# Peripherals.net
KiCad netlist of a schematic drawn in Altium Designer
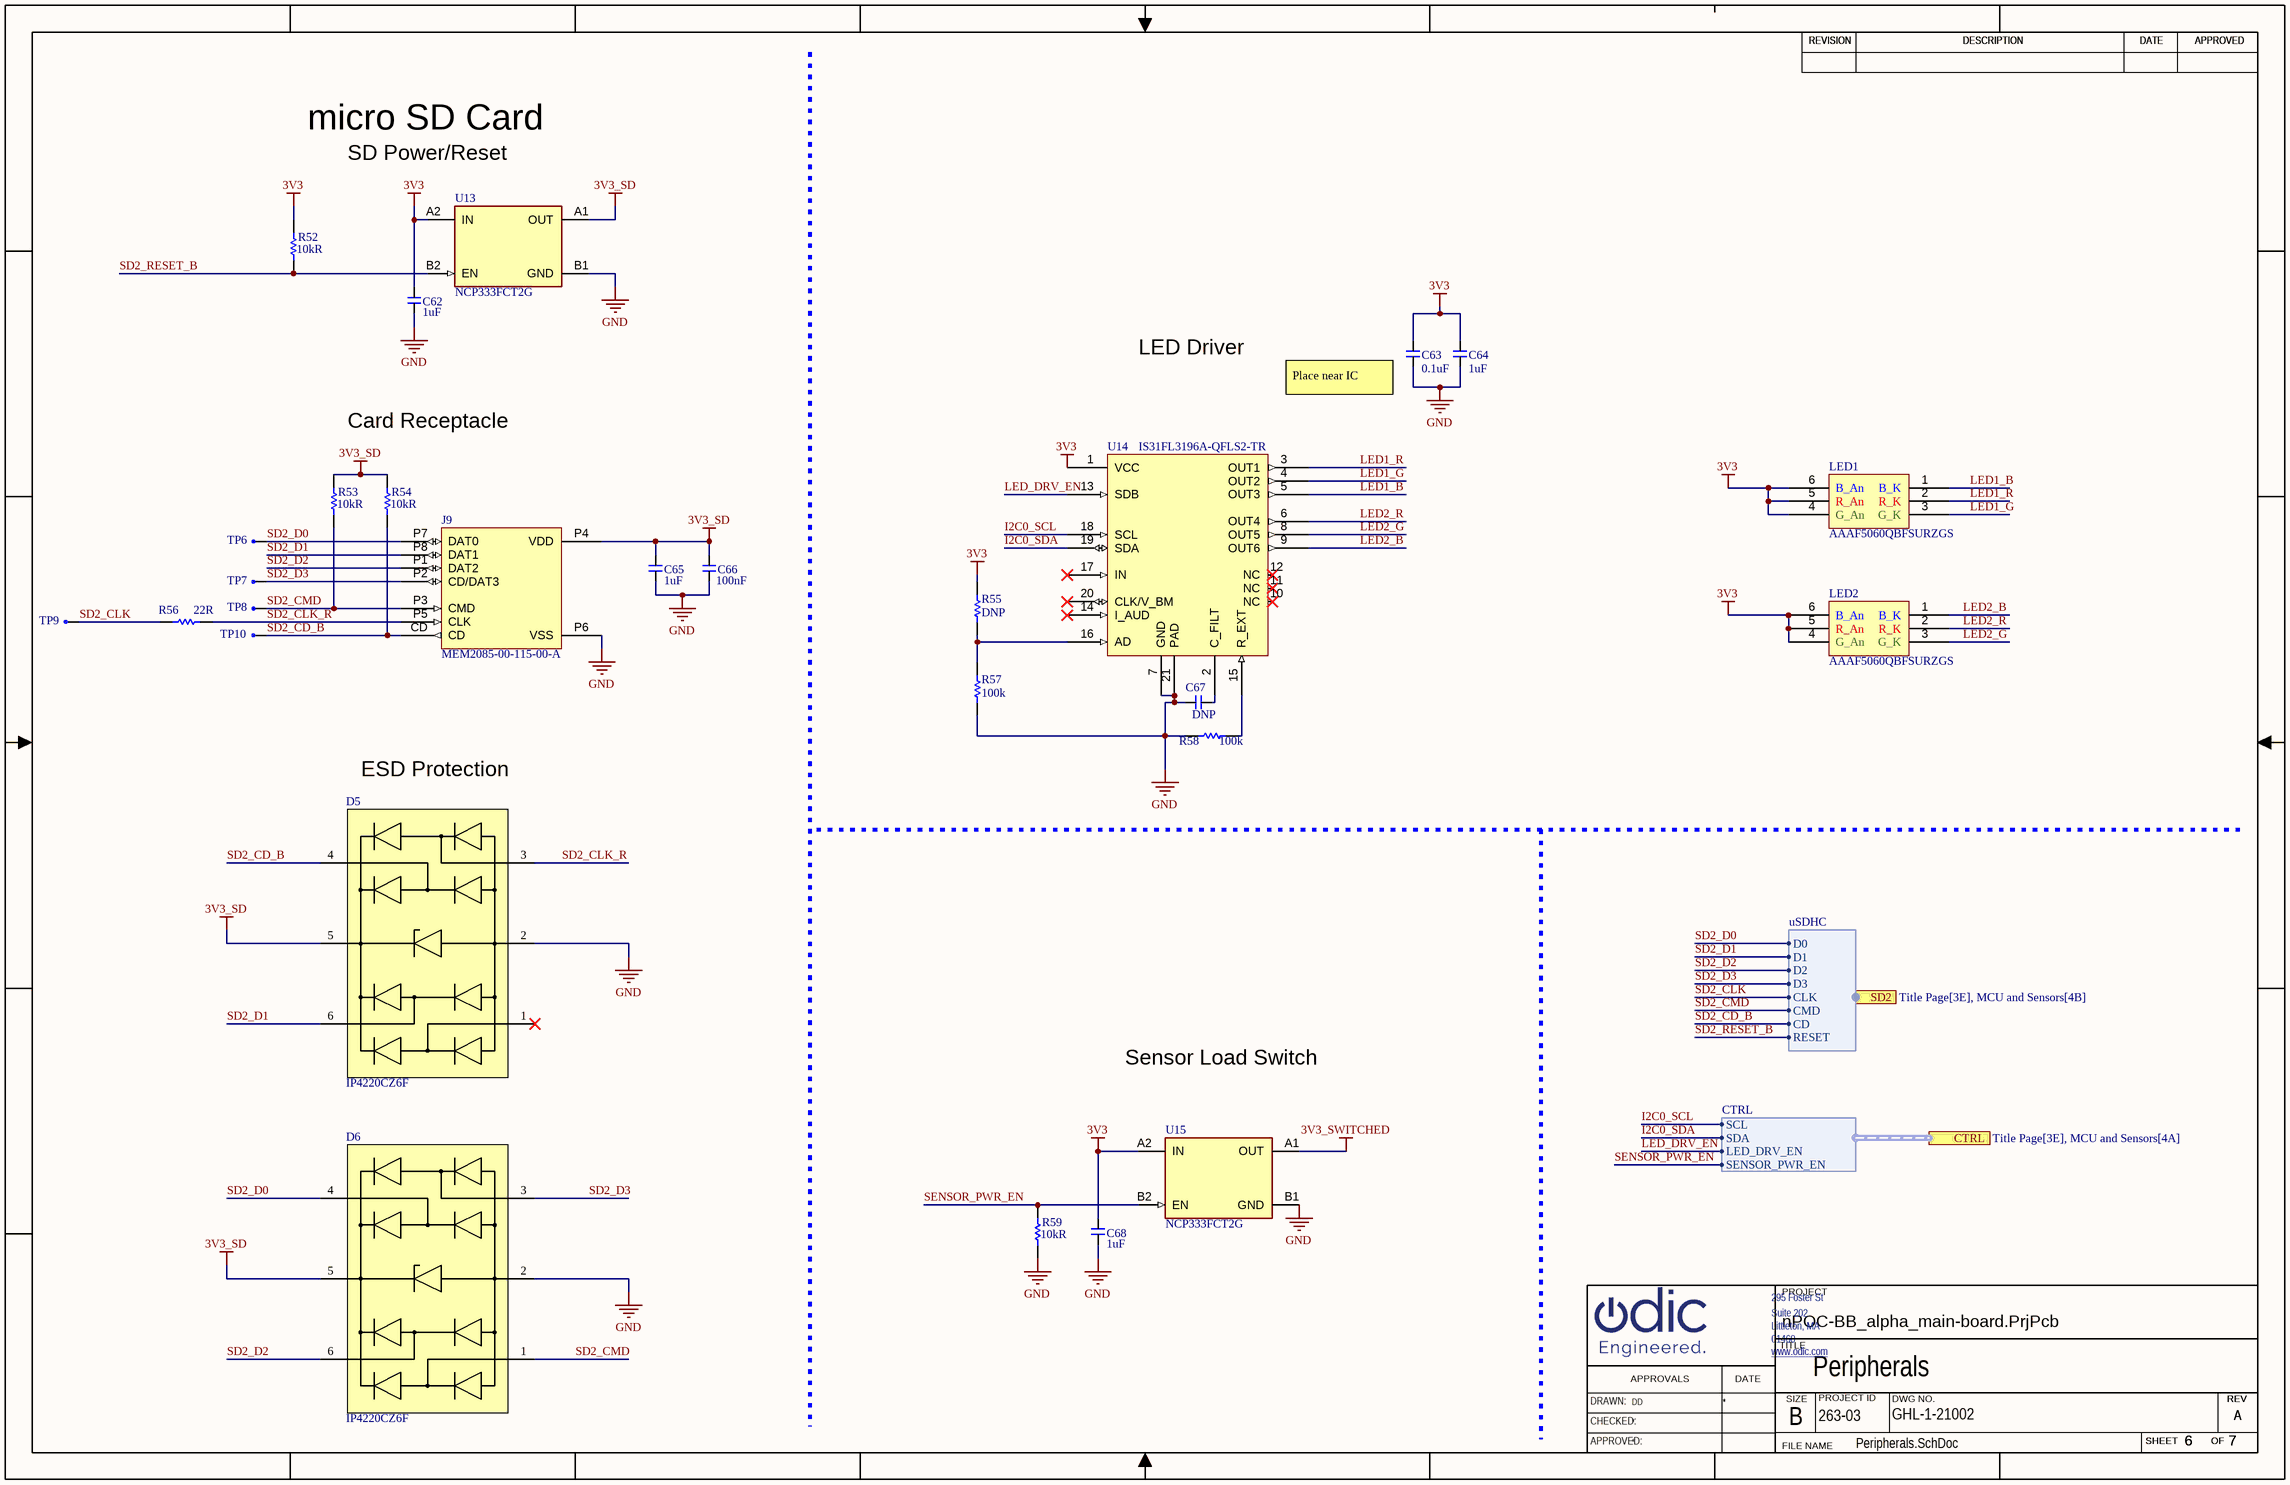
[diagram p0: Peripherals.SchDoc]

(export (version "E")
  (design (tool "Eeschema 10.0.6"))
  (components
    (comp (ref "C62")
      (value "C0402_1u_6V3_10pct")
      (footprint "C0402")
      (description "Cap Ceramic 1uF 6.3V X5R 10% SMD 0402 85C Paper T/R")
      (fields (field (name "CAPACITANCE") "1uF") (field (name "TOLERANCE") "10%"))
      (libsource (lib "Odic Inc") (part "cAP"))
    )
    (comp (ref "C63")
      (value "0.1uF")
      (footprint "C0402")
      (description "Cap Ceramic 0.1uF 25V X5R 10% Pad SMD 0402 Multi Layer Ceramic Capacitor (MLCC)")
      (fields (field (name "VOLTAGE") "25V") (field (name "TOLERANCE") "10%"))
      (libsource (lib "Odic Inc") (part "cAP"))
    )
    (comp (ref "C64")
      (value "1uF")
      (footprint "C0402")
      (description "CAP CER 1UF 16V X5R 0402")
      (fields (field (name "VOLTAGE") "16V") (field (name "TOLERANCE") "10%"))
      (libsource (lib "Odic Inc") (part "cAP"))
    )
    (comp (ref "C65")
      (value "C0402_1u_6V3_10pct")
      (footprint "C0402")
      (description "Cap Ceramic 1uF 6.3V X5R 10% SMD 0402 85C Paper T/R")
      (fields (field (name "CAPACITANCE") "1uF") (field (name "TOLERANCE") "10%"))
      (libsource (lib "Odic Inc") (part "cAP"))
    )
    (comp (ref "C66")
      (value "100nF")
      (footprint "C0402")
      (description "Ceramic capacitor SMD 0402 100nF 16V X7R 10%")
      (fields (field (name "VOLTAGE") "16V") (field (name "TOLERANCE") "10%"))
      (libsource (lib "Odic Inc") (part "cAP"))
    )
    (comp (ref "C67")
      (value "N/A")
      (footprint "C0603")
      (description "DNP CAP")
      (fields
        (field (name "MANUFACTURER") "Samsung")
        (field (name "MANUFACTURER PART NUMBER") "CL10B104KB8NNWC")
        (field (name "INSTALL") "DNP")
      )
      (libsource (lib "Odic Inc") (part "cAP"))
    )
    (comp (ref "C68")
      (value "C0402_1u_6V3_10pct")
      (footprint "C0402")
      (description "Cap Ceramic 1uF 6.3V X5R 10% SMD 0402 85C Paper T/R")
      (fields (field (name "CAPACITANCE") "1uF") (field (name "TOLERANCE") "10%"))
      (libsource (lib "Odic Inc") (part "cAP"))
    )
    (comp (ref "D5")
      (value "IP4220CZ6F")
      (footprint "SOT23-6PIN")
      (description "IC USB DUAL ESD PROTEC 6TSOP")
      (libsource (lib "Odic Inc") (part "IP4220CZ6F-symbol"))
    )
    (comp (ref "D6")
      (value "IP4220CZ6F")
      (footprint "SOT23-6PIN")
      (description "IC USB DUAL ESD PROTEC 6TSOP")
      (libsource (lib "Odic Inc") (part "IP4220CZ6F-symbol"))
    )
    (comp (ref "J9")
      (value "MEM2085-00-115-00-A")
      (footprint "GCT_MEM2085-00-115-00-A_REV0.2")
      (description "9 (8 + 1) Position Secure Digital microSD SMT Right Angle Card Connector")
      (libsource (lib "Odic Inc") (part "MEM2085-00-115-00-A-Symbol-1"))
    )
    (comp (ref "LED1")
      (value "AAAF5060QBFSURZGS")
      (footprint "led6_smt_5x6mm")
      (description "Blue/Red/Green 100º 400/800/1000 mcd Clear Surface Mount LED Lamp")
      (libsource (lib "Odic Inc") (part "AAAF5060QBFSURZGS-Symbol-1"))
    )
    (comp (ref "LED2")
      (value "AAAF5060QBFSURZGS")
      (footprint "led6_smt_5x6mm")
      (description "Blue/Red/Green 100º 400/800/1000 mcd Clear Surface Mount LED Lamp")
      (libsource (lib "Odic Inc") (part "AAAF5060QBFSURZGS-Symbol-1"))
    )
    (comp (ref "R52")
      (value "R0402_10k_1pct")
      (footprint "R0402")
      (description "Res Thick Film 0402 10K Ohm 1% 1/16W ±100ppm/°C Molded SMD SMD T/R")
      (fields (field (name "RESISTANCE") "10kR") (field (name "TOLERANCE") "1%"))
      (libsource (lib "Odic Inc") (part "RES"))
    )
    (comp (ref "R53")
      (value "R0402_10k_1pct")
      (footprint "R0402")
      (description "Res Thick Film 0402 10K Ohm 1% 1/16W ±100ppm/°C Molded SMD SMD T/R")
      (fields (field (name "RESISTANCE") "10kR") (field (name "TOLERANCE") "1%"))
      (libsource (lib "Odic Inc") (part "RES"))
    )
    (comp (ref "R54")
      (value "R0402_10k_1pct")
      (footprint "R0402")
      (description "Res Thick Film 0402 10K Ohm 1% 1/16W ±100ppm/°C Molded SMD SMD T/R")
      (fields (field (name "RESISTANCE") "10kR") (field (name "TOLERANCE") "1%"))
      (libsource (lib "Odic Inc") (part "RES"))
    )
    (comp (ref "R55")
      (value "DNP")
      (footprint "R0402")
      (description "Unpopulated 0402 pads. No part number associated with this \"component\"")
      (libsource (lib "Odic Inc") (part "RES"))
    )
    (comp (ref "R56")
      (value "R0402_22R_1pct")
      (footprint "R0402")
      (description "Res SMD 22 Ohm 1% 1/16W 0402")
      (fields (field (name "RESISTANCE") "22R"))
      (libsource (lib "Odic Inc") (part "RES"))
    )
    (comp (ref "R57")
      (value "100k")
      (footprint "R0402")
      (description "Res General Purpose Thick Film 0402 100K Ohm 1% 1/16W ±100ppm/°C Molded SMD Paper T/R")
      (fields (field (name "TOLERANCE") "1%"))
      (libsource (lib "Odic Inc") (part "RES"))
    )
    (comp (ref "R58")
      (value "100k")
      (footprint "R0402")
      (description "Res General Purpose Thick Film 0402 100K Ohm 1% 1/16W ±100ppm/°C Molded SMD Paper T/R")
      (fields (field (name "TOLERANCE") "1%"))
      (libsource (lib "Odic Inc") (part "RES"))
    )
    (comp (ref "R59")
      (value "R0402_10k_1pct")
      (footprint "R0402")
      (description "Res Thick Film 0402 10K Ohm 1% 1/16W ±100ppm/°C Molded SMD SMD T/R")
      (fields (field (name "RESISTANCE") "10kR") (field (name "TOLERANCE") "1%"))
      (libsource (lib "Odic Inc") (part "RES"))
    )
    (comp (ref "TP6")
      (value "TPC30")
      (footprint "tpc30")
      (description "Test Point Circle 30")
      (libsource (lib "Odic Inc") (part "TPC"))
    )
    (comp (ref "TP7")
      (value "TPC30")
      (footprint "tpc30")
      (description "Test Point Circle 30")
      (libsource (lib "Odic Inc") (part "TPC"))
    )
    (comp (ref "TP8")
      (value "TPC30")
      (footprint "tpc30")
      (description "Test Point Circle 30")
      (libsource (lib "Odic Inc") (part "TPC"))
    )
    (comp (ref "TP9")
      (value "TPC30")
      (footprint "tpc30")
      (description "Test Point Circle 30")
      (libsource (lib "Odic Inc") (part "TPC"))
    )
    (comp (ref "TP10")
      (value "TPC30")
      (footprint "tpc30")
      (description "Test Point Circle 30")
      (libsource (lib "Odic Inc") (part "TPC"))
    )
    (comp (ref "U13")
      (value "NCP333FCT2G")
      (footprint "bga4_p743xp743_p4mm")
      (description "IC LOAD SWITCH W/DIS 1.5A 4WLCSP")
      (libsource (lib "Odic Inc") (part "97019fd276bc7644be76e1f711e9589"))
    )
    (comp (ref "U14")
      (value "IS31FL3196A-QFLS2-TR")
      (footprint "qfn20_3x3_p4mm")
      (description "6-Channel Light Effect LED Driver with I2C Interface 2.7V to 5.5V Input 20-Pin QFN T/R")
      (libsource (lib "Odic Inc") (part "IS31FL3196A-QFLS2-TR-Symbol-1"))
    )
    (comp (ref "U15")
      (value "NCP333FCT2G")
      (footprint "bga4_p743xp743_p4mm")
      (description "IC LOAD SWITCH W/DIS 1.5A 4WLCSP")
      (libsource (lib "Odic Inc") (part "97019fd276bc7644be76e1f711e9589"))
    )
  )
  (nets
    (net (code "3") (name "/I2C0_SCL") (class "Default")
      (node (ref "U14") (pin "18") (pinfunction "SCL_18") (pintype "input"))
    )
    (net (code "4") (name "/I2C0_SDA") (class "Default")
      (node (ref "U14") (pin "19") (pinfunction "SDA_19") (pintype "bidirectional"))
    )
    (net (code "5") (name "/LED1_B") (class "Default")
      (node (ref "LED1") (pin "1") (pinfunction "B_K_1") (pintype "passive"))
      (node (ref "U14") (pin "5") (pinfunction "OUT3_5") (pintype "output"))
    )
    (net (code "6") (name "/LED1_G") (class "Default")
      (node (ref "LED1") (pin "3") (pinfunction "G_K_3") (pintype "passive"))
      (node (ref "U14") (pin "4") (pinfunction "OUT2_4") (pintype "output"))
    )
    (net (code "7") (name "/LED1_R") (class "Default")
      (node (ref "LED1") (pin "2") (pinfunction "R_K_2") (pintype "passive"))
      (node (ref "U14") (pin "3") (pinfunction "OUT1_3") (pintype "output"))
    )
    (net (code "8") (name "/LED2_B") (class "Default")
      (node (ref "LED2") (pin "1") (pinfunction "B_K_1") (pintype "passive"))
      (node (ref "U14") (pin "9") (pinfunction "OUT6_9") (pintype "output"))
    )
    (net (code "9") (name "/LED2_G") (class "Default")
      (node (ref "LED2") (pin "3") (pinfunction "G_K_3") (pintype "passive"))
      (node (ref "U14") (pin "8") (pinfunction "OUT5_8") (pintype "output"))
    )
    (net (code "10") (name "/LED2_R") (class "Default")
      (node (ref "LED2") (pin "2") (pinfunction "R_K_2") (pintype "passive"))
      (node (ref "U14") (pin "6") (pinfunction "OUT4_6") (pintype "output"))
    )
    (net (code "11") (name "/LED_DRV_EN") (class "Default")
      (node (ref "U14") (pin "13") (pinfunction "SDB_13") (pintype "input"))
    )
    (net (code "12") (name "/SD2_CD_B") (class "Default")
      (node (ref "D5") (pin "4") (pinfunction "I/O3_4") (pintype "passive"))
      (node (ref "J9") (pin "CD") (pinfunction "CD_CD") (pintype "output"))
      (node (ref "R54") (pin "2") (pinfunction "2_2") (pintype "passive"))
      (node (ref "TP10") (pin "1") (pinfunction "1_1") (pintype "passive"))
    )
    (net (code "13") (name "/SD2_CLK") (class "Default")
      (node (ref "R56") (pin "1") (pinfunction "1_1") (pintype "passive"))
      (node (ref "TP9") (pin "1") (pinfunction "1_1") (pintype "passive"))
    )
    (net (code "14") (name "/SD2_CLK_R") (class "Default")
      (node (ref "D5") (pin "3") (pinfunction "I/O2_3") (pintype "passive"))
      (node (ref "J9") (pin "P5") (pinfunction "CLK_P5") (pintype "input"))
      (node (ref "R56") (pin "2") (pinfunction "2_2") (pintype "passive"))
    )
    (net (code "15") (name "/SD2_CMD") (class "Default")
      (node (ref "D6") (pin "1") (pinfunction "I/O1_1") (pintype "passive"))
      (node (ref "J9") (pin "P3") (pinfunction "CMD_P3") (pintype "input"))
      (node (ref "R53") (pin "2") (pinfunction "2_2") (pintype "passive"))
      (node (ref "TP8") (pin "1") (pinfunction "1_1") (pintype "passive"))
    )
    (net (code "16") (name "/SD2_D0") (class "Default")
      (node (ref "D6") (pin "4") (pinfunction "I/O3_4") (pintype "passive"))
      (node (ref "J9") (pin "P7") (pinfunction "DAT0_P7") (pintype "bidirectional"))
      (node (ref "TP6") (pin "1") (pinfunction "1_1") (pintype "passive"))
    )
    (net (code "17") (name "/SD2_D1") (class "Default")
      (node (ref "D5") (pin "6") (pinfunction "I/O4_6") (pintype "passive"))
      (node (ref "J9") (pin "P8") (pinfunction "DAT1_P8") (pintype "bidirectional"))
    )
    (net (code "18") (name "/SD2_D2") (class "Default")
      (node (ref "D6") (pin "6") (pinfunction "I/O4_6") (pintype "passive"))
      (node (ref "J9") (pin "P1") (pinfunction "DAT2_P1") (pintype "bidirectional"))
    )
    (net (code "19") (name "/SD2_D3") (class "Default")
      (node (ref "D6") (pin "3") (pinfunction "I/O2_3") (pintype "passive"))
      (node (ref "J9") (pin "P2") (pinfunction "CD/DAT3_P2") (pintype "bidirectional"))
      (node (ref "TP7") (pin "1") (pinfunction "1_1") (pintype "passive"))
    )
    (net (code "20") (name "/SD2_RESET_B") (class "Default")
      (node (ref "R52") (pin "2") (pinfunction "2_2") (pintype "passive"))
      (node (ref "U13") (pin "B2") (pinfunction "EN_B2") (pintype "input"))
    )
    (net (code "21") (name "/SENSOR_PWR_EN") (class "Default")
      (node (ref "R59") (pin "1") (pinfunction "1_1") (pintype "passive"))
      (node (ref "U15") (pin "B2") (pinfunction "EN_B2") (pintype "input"))
    )
    (net (code "24") (name "3V3") (class "Default")
      (node (ref "C62") (pin "2") (pinfunction "2_2") (pintype "passive"))
      (node (ref "C63") (pin "2") (pinfunction "2_2") (pintype "passive"))
      (node (ref "C64") (pin "2") (pinfunction "2_2") (pintype "passive"))
      (node (ref "C68") (pin "2") (pinfunction "2_2") (pintype "passive"))
      (node (ref "LED1") (pin "4") (pinfunction "G_An_4") (pintype "passive"))
      (node (ref "LED1") (pin "5") (pinfunction "R_An_5") (pintype "passive"))
      (node (ref "LED1") (pin "6") (pinfunction "B_An_6") (pintype "passive"))
      (node (ref "LED2") (pin "4") (pinfunction "G_An_4") (pintype "passive"))
      (node (ref "LED2") (pin "5") (pinfunction "R_An_5") (pintype "passive"))
      (node (ref "LED2") (pin "6") (pinfunction "B_An_6") (pintype "passive"))
      (node (ref "R52") (pin "1") (pinfunction "1_1") (pintype "passive"))
      (node (ref "R55") (pin "2") (pinfunction "2_2") (pintype "passive"))
      (node (ref "U13") (pin "A2") (pinfunction "IN_A2") (pintype "power_in"))
      (node (ref "U14") (pin "1") (pinfunction "VCC_1") (pintype "power_in"))
      (node (ref "U15") (pin "A2") (pinfunction "IN_A2") (pintype "power_in"))
    )
    (net (code "25") (name "3V3_SD") (class "Default")
      (node (ref "C65") (pin "2") (pinfunction "2_2") (pintype "passive"))
      (node (ref "C66") (pin "2") (pinfunction "2_2") (pintype "passive"))
      (node (ref "D5") (pin "5") (pinfunction "VP_5") (pintype "power_in"))
      (node (ref "D6") (pin "5") (pinfunction "VP_5") (pintype "power_in"))
      (node (ref "J9") (pin "P4") (pinfunction "VDD_P4") (pintype "passive"))
      (node (ref "R53") (pin "1") (pinfunction "1_1") (pintype "passive"))
      (node (ref "R54") (pin "1") (pinfunction "1_1") (pintype "passive"))
      (node (ref "U13") (pin "A1") (pinfunction "OUT_A1") (pintype "power_in"))
    )
    (net (code "26") (name "3V3_SWITCHED") (class "Default")
      (node (ref "U15") (pin "A1") (pinfunction "OUT_A1") (pintype "power_in"))
    )
    (net (code "27") (name "GND") (class "Default")
      (node (ref "C62") (pin "1") (pinfunction "1_1") (pintype "passive"))
      (node (ref "C63") (pin "1") (pinfunction "1_1") (pintype "passive"))
      (node (ref "C64") (pin "1") (pinfunction "1_1") (pintype "passive"))
      (node (ref "C65") (pin "1") (pinfunction "1_1") (pintype "passive"))
      (node (ref "C66") (pin "1") (pinfunction "1_1") (pintype "passive"))
      (node (ref "C67") (pin "2") (pinfunction "2_2") (pintype "passive"))
      (node (ref "C68") (pin "1") (pinfunction "1_1") (pintype "passive"))
      (node (ref "D5") (pin "2") (pinfunction "GND_2") (pintype "power_in"))
      (node (ref "D6") (pin "2") (pinfunction "GND_2") (pintype "power_in"))
      (node (ref "J9") (pin "P6") (pinfunction "VSS_P6") (pintype "passive"))
      (node (ref "R57") (pin "1") (pinfunction "1_1") (pintype "passive"))
      (node (ref "R58") (pin "2") (pinfunction "2_2") (pintype "passive"))
      (node (ref "R59") (pin "2") (pinfunction "2_2") (pintype "passive"))
      (node (ref "U13") (pin "B1") (pinfunction "GND_B1") (pintype "power_in"))
      (node (ref "U14") (pin "21") (pinfunction "PAD_21") (pintype "passive"))
      (node (ref "U14") (pin "7") (pinfunction "GND_7") (pintype "passive"))
      (node (ref "U15") (pin "B1") (pinfunction "GND_B1") (pintype "power_in"))
    )
    (net (code "28") (name "Net-(U14-AD)") (class "Default")
      (node (ref "R55") (pin "1") (pinfunction "1_1") (pintype "passive"))
      (node (ref "R57") (pin "2") (pinfunction "2_2") (pintype "passive"))
      (node (ref "U14") (pin "16") (pinfunction "AD_16") (pintype "input"))
    )
    (net (code "29") (name "Net-(U14-C_FILT)") (class "Default")
      (node (ref "C67") (pin "1") (pinfunction "1_1") (pintype "passive"))
      (node (ref "U14") (pin "2") (pinfunction "C_FILT_2") (pintype "passive"))
    )
    (net (code "30") (name "Net-(U14-R_EXT)") (class "Default")
      (node (ref "R58") (pin "1") (pinfunction "1_1") (pintype "passive"))
      (node (ref "U14") (pin "15") (pinfunction "R_EXT_15") (pintype "input"))
    )
    (net (code "31") (name "unconnected-(D5-I{slash}O1-Pad1)") (class "Default")
      (node (ref "D5") (pin "1") (pinfunction "I/O1_1") (pintype "passive+no_connect"))
    )
    (net (code "32") (name "unconnected-(U14-CLK{slash}V_BM-Pad20)") (class "Default")
      (node (ref "U14") (pin "20") (pinfunction "CLK/V_BM_20") (pintype "bidirectional+no_connect"))
    )
    (net (code "33") (name "unconnected-(U14-IN-Pad17)") (class "Default")
      (node (ref "U14") (pin "17") (pinfunction "IN_17") (pintype "input+no_connect"))
    )
    (net (code "34") (name "unconnected-(U14-I_AUD-Pad14)") (class "Default")
      (node (ref "U14") (pin "14") (pinfunction "I_AUD_14") (pintype "input+no_connect"))
    )
    (net (code "35") (name "unconnected-(U14-NC-Pad10)") (class "Default")
      (node (ref "U14") (pin "10") (pinfunction "NC_10") (pintype "passive+no_connect"))
    )
    (net (code "36") (name "unconnected-(U14-NC-Pad11)") (class "Default")
      (node (ref "U14") (pin "11") (pinfunction "NC_11") (pintype "passive+no_connect"))
    )
    (net (code "37") (name "unconnected-(U14-NC-Pad12)") (class "Default")
      (node (ref "U14") (pin "12") (pinfunction "NC_12") (pintype "passive+no_connect"))
    )
  )
)
